# OpenChair.net
KiCad netlist of a schematic drawn in EAGLE
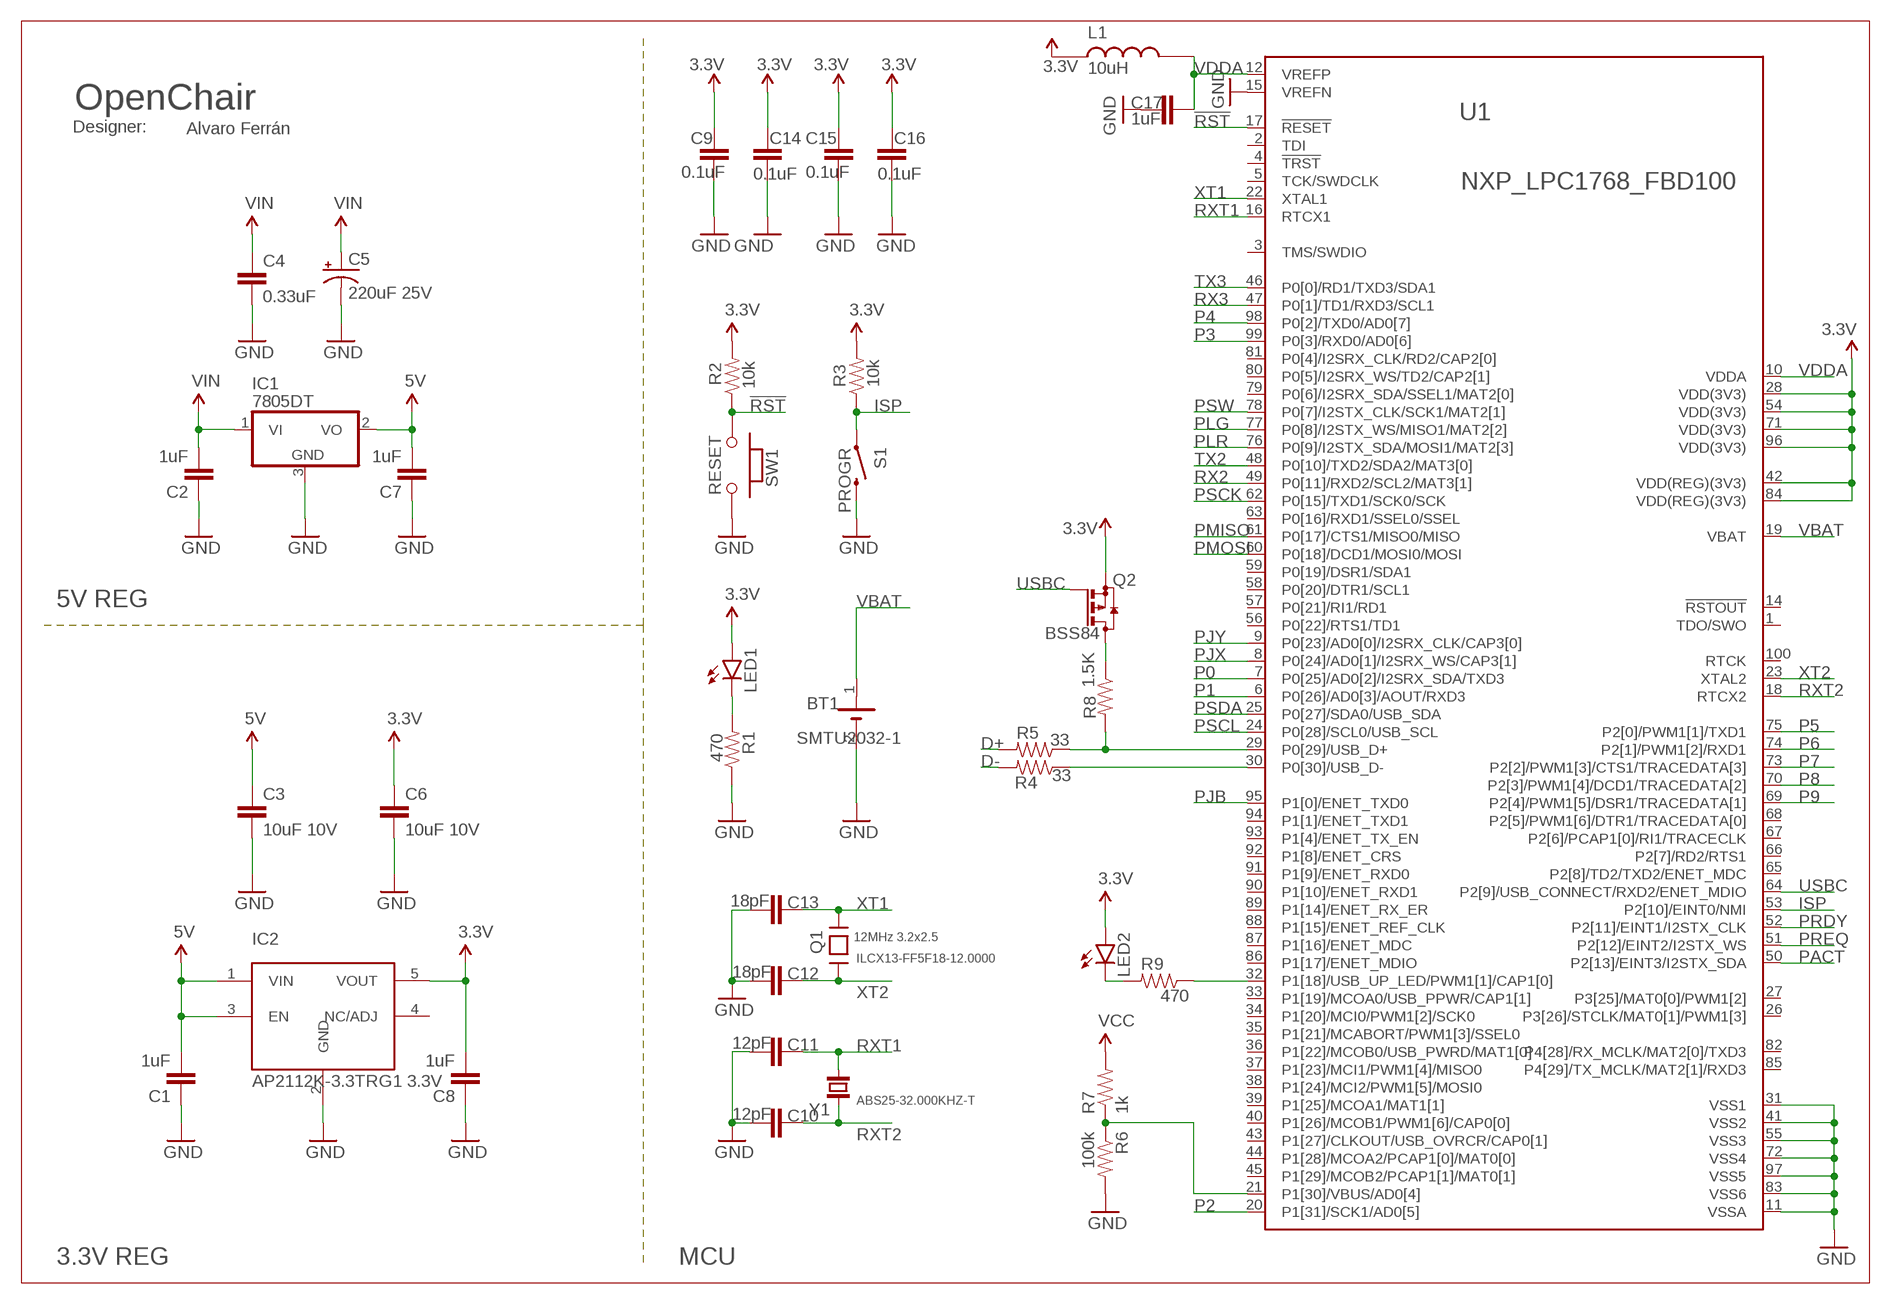
[diagram p0: schematic, sheet 1]
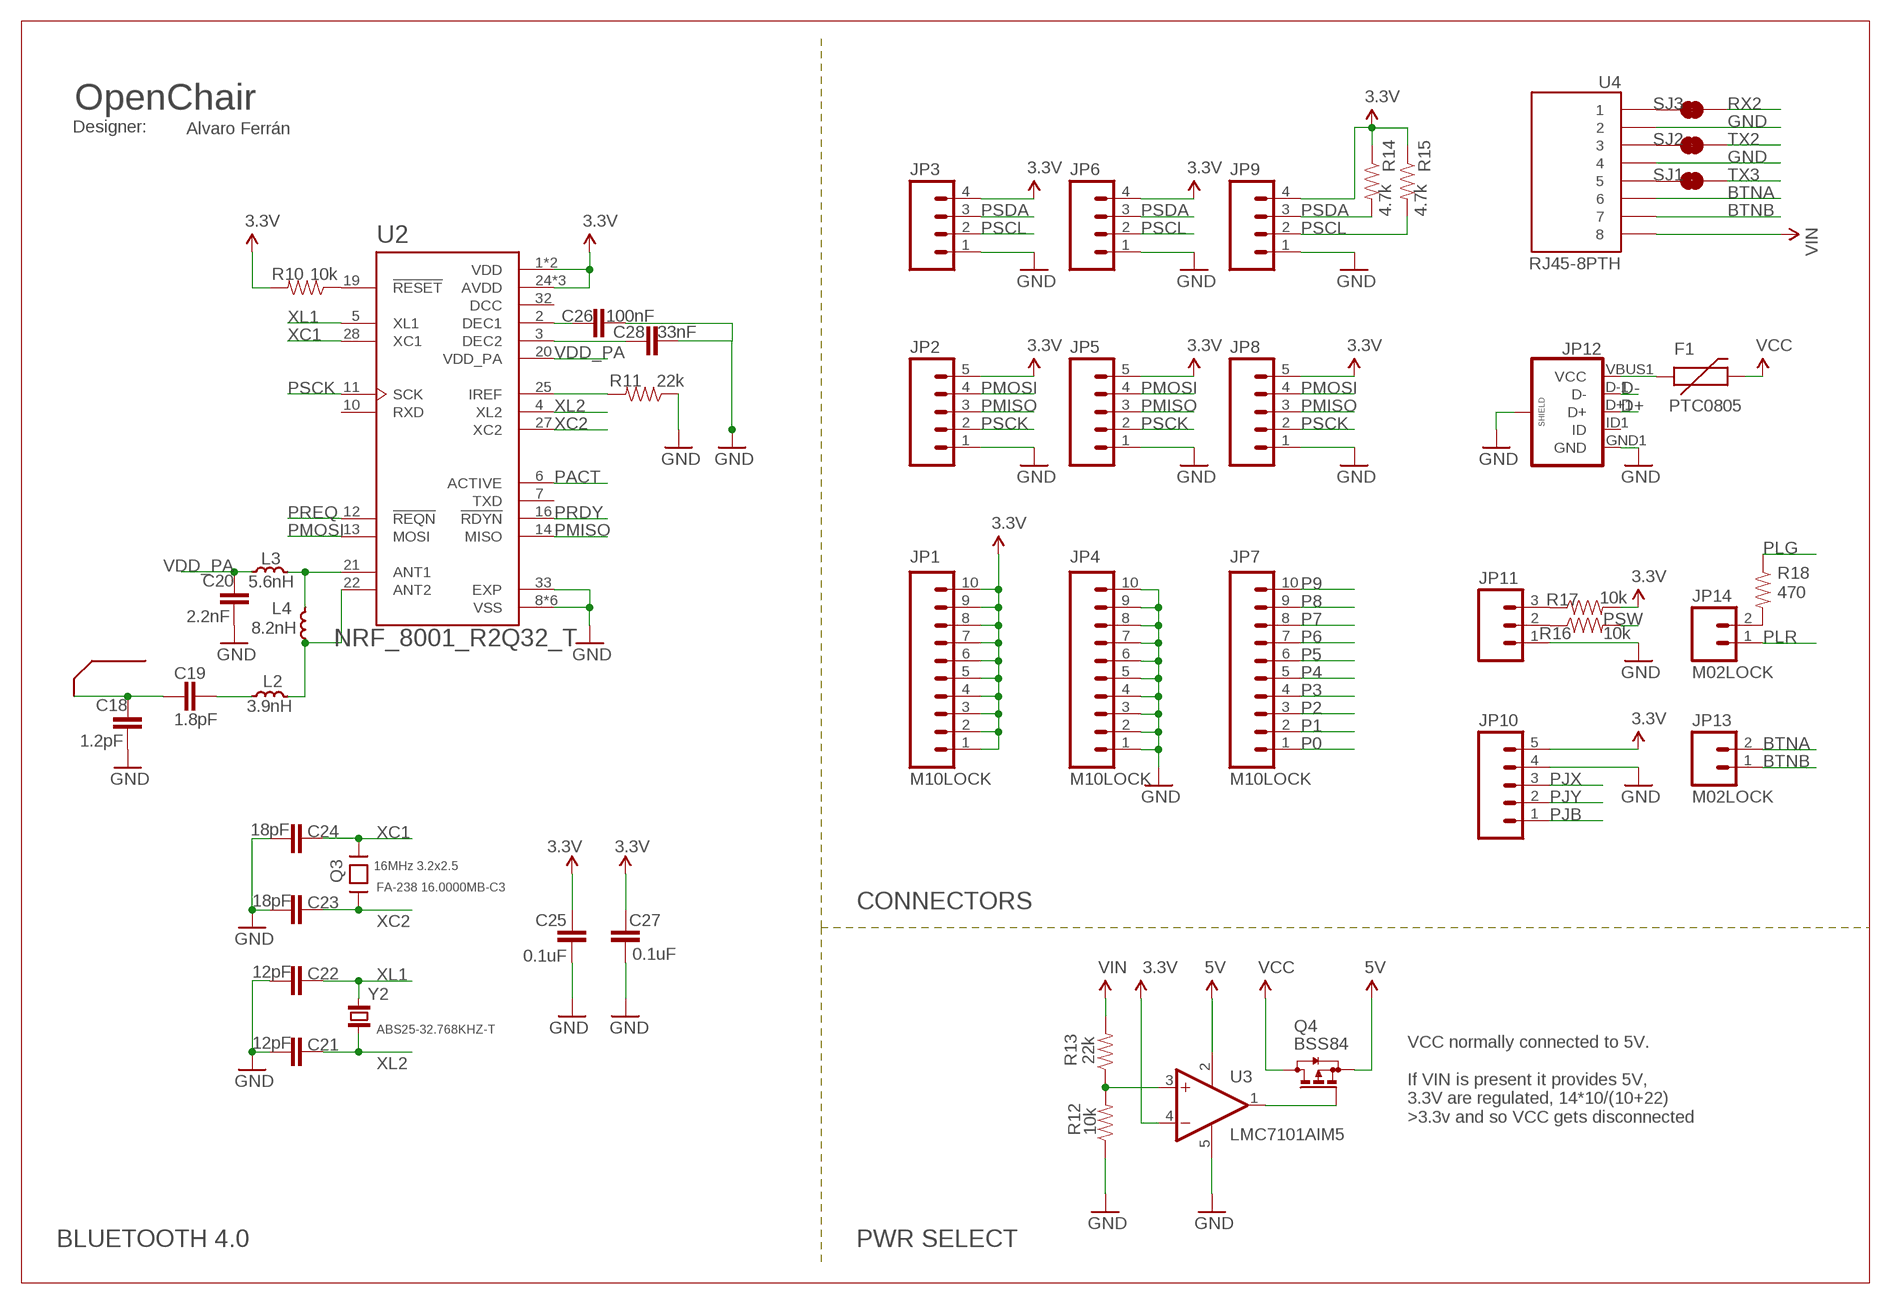
[diagram p1: schematic, sheet 2]

(export (version "E")
  (design (tool "Eeschema 10.0.6"))
  (components
    (comp (ref "ANT1")
      (value "NRF_ANTENNA")
      (footprint "eagle-import:NRF_ANTENNA")
      (libsource (lib "eagle-import") (part "NRF_ANTENNA"))
    )
    (comp (ref "C18")
      (value "1.2pF")
      (footprint "eagle-import:0402-CAP")
      (libsource (lib "eagle-import") (part "CAP0402-CAP"))
    )
    (comp (ref "C19")
      (value "1.8pF")
      (footprint "eagle-import:0402-CAP")
      (libsource (lib "eagle-import") (part "CAP0402-CAP"))
    )
    (comp (ref "C20")
      (value "2.2nF")
      (footprint "eagle-import:0402-CAP")
      (libsource (lib "eagle-import") (part "CAP0402-CAP"))
    )
    (comp (ref "C21")
      (value "12pF")
      (footprint "eagle-import:0402-CAP")
      (libsource (lib "eagle-import") (part "CAP0402-CAP"))
    )
    (comp (ref "C22")
      (value "12pF")
      (footprint "eagle-import:0402-CAP")
      (libsource (lib "eagle-import") (part "CAP0402-CAP"))
    )
    (comp (ref "C23")
      (value "18pF")
      (footprint "eagle-import:0402-CAP")
      (libsource (lib "eagle-import") (part "CAP0402-CAP"))
    )
    (comp (ref "C24")
      (value "18pF")
      (footprint "eagle-import:0402-CAP")
      (libsource (lib "eagle-import") (part "CAP0402-CAP"))
    )
    (comp (ref "C25")
      (value "0.1uF")
      (footprint "eagle-import:0402-CAP")
      (libsource (lib "eagle-import") (part "CAP0402-CAP"))
    )
    (comp (ref "C26")
      (value "100nF")
      (footprint "eagle-import:0402-CAP")
      (libsource (lib "eagle-import") (part "CAP0402-CAP"))
    )
    (comp (ref "C27")
      (value "0.1uF")
      (footprint "eagle-import:0402-CAP")
      (libsource (lib "eagle-import") (part "CAP0402-CAP"))
    )
    (comp (ref "C28")
      (value "33nF")
      (footprint "eagle-import:0402-CAP")
      (libsource (lib "eagle-import") (part "CAP0402-CAP"))
    )
    (comp (ref "F1")
      (value "PTC0805")
      (footprint "eagle-import:0805")
      (libsource (lib "eagle-import") (part "PTC0805"))
    )
    (comp (ref "JP1")
      (value "M10LOCK")
      (footprint "eagle-import:1X10_LOCK")
      (libsource (lib "eagle-import") (part "M10LOCK"))
    )
    (comp (ref "JP2")
      (value "M05LOCK")
      (footprint "eagle-import:1X05_LOCK")
      (libsource (lib "eagle-import") (part "M05LOCK"))
    )
    (comp (ref "JP3")
      (value "M04LOCK")
      (footprint "eagle-import:1X04_LOCK")
      (libsource (lib "eagle-import") (part "M04LOCK"))
    )
    (comp (ref "JP4")
      (value "M10LOCK")
      (footprint "eagle-import:1X10_LOCK")
      (libsource (lib "eagle-import") (part "M10LOCK"))
    )
    (comp (ref "JP5")
      (value "M05LOCK")
      (footprint "eagle-import:1X05_LOCK")
      (libsource (lib "eagle-import") (part "M05LOCK"))
    )
    (comp (ref "JP6")
      (value "M04LOCK")
      (footprint "eagle-import:1X04_LOCK")
      (libsource (lib "eagle-import") (part "M04LOCK"))
    )
    (comp (ref "JP7")
      (value "M10LOCK")
      (footprint "eagle-import:1X10_LOCK")
      (libsource (lib "eagle-import") (part "M10LOCK"))
    )
    (comp (ref "JP8")
      (value "M05LOCK")
      (footprint "eagle-import:1X05_LOCK")
      (libsource (lib "eagle-import") (part "M05LOCK"))
    )
    (comp (ref "JP9")
      (value "M04LOCK")
      (footprint "eagle-import:1X04_LOCK")
      (libsource (lib "eagle-import") (part "M04LOCK"))
    )
    (comp (ref "JP10")
      (value "M05LOCK")
      (footprint "eagle-import:1X05_LOCK")
      (libsource (lib "eagle-import") (part "M05LOCK"))
    )
    (comp (ref "JP11")
      (value "M03LOCK")
      (footprint "eagle-import:1X03_LOCK")
      (libsource (lib "eagle-import") (part "M03LOCK"))
    )
    (comp (ref "JP12")
      (value "USB_MICROB_PLUGCONN-11752")
      (footprint "eagle-import:USB-B-MICRO-SMD_V03")
      (libsource (lib "eagle-import") (part "USB_MICROB_PLUGCONN-11752"))
    )
    (comp (ref "JP13")
      (value "M02LOCK")
      (footprint "eagle-import:1X02_LOCK")
      (libsource (lib "eagle-import") (part "M02LOCK"))
    )
    (comp (ref "JP14")
      (value "M02LOCK")
      (footprint "eagle-import:1X02_LOCK")
      (libsource (lib "eagle-import") (part "M02LOCK"))
    )
    (comp (ref "L2")
      (value "3.9nH")
      (footprint "eagle-import:0402")
      (libsource (lib "eagle-import") (part "L0402"))
    )
    (comp (ref "L3")
      (value "5.6nH")
      (footprint "eagle-import:0402")
      (libsource (lib "eagle-import") (part "L0402"))
    )
    (comp (ref "L4")
      (value "8.2nH")
      (footprint "eagle-import:0402")
      (libsource (lib "eagle-import") (part "L0402"))
    )
    (comp (ref "Q3")
      (value "16MHz 3.2x2.5")
      (footprint "eagle-import:CRYSTAL_3.2X2.5")
      (libsource (lib "eagle-import") (part "CRYSTAL3.2X2.5"))
    )
    (comp (ref "Q4")
      (value "BSS84")
      (footprint "eagle-import:SOT23")
      (libsource (lib "eagle-import") (part "BSS84"))
    )
    (comp (ref "R10")
      (value "10k")
      (footprint "eagle-import:0402-RES")
      (libsource (lib "eagle-import") (part "RESISTOR0402-RES"))
    )
    (comp (ref "R11")
      (value "22k")
      (footprint "eagle-import:0402-RES")
      (libsource (lib "eagle-import") (part "RESISTOR0402-RES"))
    )
    (comp (ref "R12")
      (value "10k")
      (footprint "eagle-import:0402-RES")
      (libsource (lib "eagle-import") (part "RESISTOR0402-RES"))
    )
    (comp (ref "R13")
      (value "22k")
      (footprint "eagle-import:0402-RES")
      (libsource (lib "eagle-import") (part "RESISTOR0402-RES"))
    )
    (comp (ref "R14")
      (value "4.7k")
      (footprint "eagle-import:0402-RES")
      (libsource (lib "eagle-import") (part "RESISTOR0402-RES"))
    )
    (comp (ref "R15")
      (value "4.7k")
      (footprint "eagle-import:0402-RES")
      (libsource (lib "eagle-import") (part "RESISTOR0402-RES"))
    )
    (comp (ref "R16")
      (value "10k")
      (footprint "eagle-import:0402-RES")
      (libsource (lib "eagle-import") (part "RESISTOR0402-RES"))
    )
    (comp (ref "R17")
      (value "10k")
      (footprint "eagle-import:0402-RES")
      (libsource (lib "eagle-import") (part "RESISTOR0402-RES"))
    )
    (comp (ref "R18")
      (value "470")
      (footprint "eagle-import:0402-RES")
      (libsource (lib "eagle-import") (part "RESISTOR0402-RES"))
    )
    (comp (ref "SJ1")
      (value "JUMPER-PAD-2-NC_BY_TRACE")
      (footprint "eagle-import:PAD-JUMPER-2-NC_BY_TRACE_YES_SILK")
      (libsource (lib "eagle-import") (part "JUMPER-PAD-2-NC_BY_TRACE"))
    )
    (comp (ref "SJ2")
      (value "JUMPER-PAD-2-NC_BY_TRACE")
      (footprint "eagle-import:PAD-JUMPER-2-NC_BY_TRACE_YES_SILK")
      (libsource (lib "eagle-import") (part "JUMPER-PAD-2-NC_BY_TRACE"))
    )
    (comp (ref "SJ3")
      (value "JUMPER-PAD-2-NC_BY_TRACE")
      (footprint "eagle-import:PAD-JUMPER-2-NC_BY_TRACE_YES_SILK")
      (libsource (lib "eagle-import") (part "JUMPER-PAD-2-NC_BY_TRACE"))
    )
    (comp (ref "U2")
      (value "NRF_8001_R2Q32_T")
      (footprint "eagle-import:QFN50P500X500X90-33N")
      (fields (field (name "MF") "Nordic Semiconductor") (field (name "MP") "NRF8001-R2Q32-T"))
      (libsource (lib "eagle-import") (part "NRF_8001_R2Q32_T"))
    )
    (comp (ref "U3")
      (value "LMC7101AIM5")
      (footprint "eagle-import:SOT23-5")
      (libsource (lib "eagle-import") (part "LMC7101AIM5"))
    )
    (comp (ref "U4")
      (value "RJ45-8PTH")
      (footprint "eagle-import:RJ45-8")
      (libsource (lib "eagle-import") (part "RJ45-8PTH"))
    )
    (comp (ref "Y2")
      (value "ABS25-32.768kHz")
      (footprint "eagle-import:ABS25")
      (fields (field (name "MF") "Abracon") (field (name "MP") "ABS25-32.000KHZ-T"))
      (libsource (lib "eagle-import") (part "ABS25"))
    )
    (comp (ref "BT1")
      (value "SMTU2032-1")
      (footprint "eagle-import:RENATA_SMTU2032-1")
      (fields (field (name "MF") "Renata") (field (name "MP") "SMTU2032-LF.TR"))
      (libsource (lib "eagle-import") (part "SMTU2032-1"))
    )
    (comp (ref "C1")
      (value "1uF")
      (footprint "eagle-import:0603-CAP")
      (libsource (lib "eagle-import") (part "CAP0603-CAP"))
    )
    (comp (ref "C2")
      (value "1uF")
      (footprint "eagle-import:0603-CAP")
      (libsource (lib "eagle-import") (part "CAP0603-CAP"))
    )
    (comp (ref "C3")
      (value "10uF 10V")
      (footprint "eagle-import:0603-CAP")
      (libsource (lib "eagle-import") (part "CAP0603-CAP"))
    )
    (comp (ref "C4")
      (value "0.33uF")
      (footprint "eagle-import:0805")
      (libsource (lib "eagle-import") (part "CAP0805"))
    )
    (comp (ref "C5")
      (value "220uF 25V")
      (footprint "eagle-import:CPOL-RADIAL-100UF-25V")
      (libsource (lib "eagle-import") (part "CAP_POLPTH1"))
    )
    (comp (ref "C6")
      (value "10uF 10V")
      (footprint "eagle-import:0603-CAP")
      (libsource (lib "eagle-import") (part "CAP0603-CAP"))
    )
    (comp (ref "C7")
      (value "1uF")
      (footprint "eagle-import:0603-CAP")
      (libsource (lib "eagle-import") (part "CAP0603-CAP"))
    )
    (comp (ref "C8")
      (value "1uF")
      (footprint "eagle-import:0603-CAP")
      (libsource (lib "eagle-import") (part "CAP0603-CAP"))
    )
    (comp (ref "C9")
      (value "0.1uF")
      (footprint "eagle-import:0402-CAP")
      (libsource (lib "eagle-import") (part "CAP0402-CAP"))
    )
    (comp (ref "C10")
      (value "12pF")
      (footprint "eagle-import:0402-CAP")
      (libsource (lib "eagle-import") (part "CAP0402-CAP"))
    )
    (comp (ref "C11")
      (value "12pF")
      (footprint "eagle-import:0402-CAP")
      (libsource (lib "eagle-import") (part "CAP0402-CAP"))
    )
    (comp (ref "C12")
      (value "18pF")
      (footprint "eagle-import:0402-CAP")
      (libsource (lib "eagle-import") (part "CAP0402-CAP"))
    )
    (comp (ref "C13")
      (value "18pF")
      (footprint "eagle-import:0402-CAP")
      (libsource (lib "eagle-import") (part "CAP0402-CAP"))
    )
    (comp (ref "C14")
      (value "0.1uF")
      (footprint "eagle-import:0402-CAP")
      (libsource (lib "eagle-import") (part "CAP0402-CAP"))
    )
    (comp (ref "C15")
      (value "0.1uF")
      (footprint "eagle-import:0402-CAP")
      (libsource (lib "eagle-import") (part "CAP0402-CAP"))
    )
    (comp (ref "C16")
      (value "0.1uF")
      (footprint "eagle-import:0402-CAP")
      (libsource (lib "eagle-import") (part "CAP0402-CAP"))
    )
    (comp (ref "C17")
      (value "1uF")
      (footprint "eagle-import:0603-CAP")
      (libsource (lib "eagle-import") (part "CAP0603-CAP"))
    )
    (comp (ref "IC1")
      (value "7805DT")
      (footprint "eagle-import:TO252")
      (libsource (lib "eagle-import") (part "78DT05"))
    )
    (comp (ref "IC2")
      (value "AP2112K-3.3TRG1 3.3V")
      (footprint "eagle-import:SOT23-5")
      (libsource (lib "eagle-import") (part "5PIN_REG"))
    )
    (comp (ref "L1")
      (value "10uH")
      (footprint "eagle-import:L0603")
      (libsource (lib "eagle-import") (part "L_L"))
    )
    (comp (ref "LED1")
      (value "LED0603")
      (footprint "eagle-import:LED-0603")
      (libsource (lib "eagle-import") (part "LED0603"))
    )
    (comp (ref "LED2")
      (value "LED0603")
      (footprint "eagle-import:LED-0603")
      (libsource (lib "eagle-import") (part "LED0603"))
    )
    (comp (ref "Q1")
      (value "12MHz 3.2x2.5")
      (footprint "eagle-import:CRYSTAL_3.2X2.5")
      (libsource (lib "eagle-import") (part "CRYSTAL3.2X2.5"))
    )
    (comp (ref "Q2")
      (value "BSS84")
      (footprint "eagle-import:SOT23")
      (libsource (lib "eagle-import") (part "BSS84"))
    )
    (comp (ref "R1")
      (value "470")
      (footprint "eagle-import:0402-RES")
      (libsource (lib "eagle-import") (part "RESISTOR0402-RES"))
    )
    (comp (ref "R2")
      (value "10k")
      (footprint "eagle-import:0402-RES")
      (libsource (lib "eagle-import") (part "RESISTOR0402-RES"))
    )
    (comp (ref "R3")
      (value "10k")
      (footprint "eagle-import:0402-RES")
      (libsource (lib "eagle-import") (part "RESISTOR0402-RES"))
    )
    (comp (ref "R4")
      (value "33")
      (footprint "eagle-import:0402-RES")
      (libsource (lib "eagle-import") (part "RESISTOR0402-RES"))
    )
    (comp (ref "R5")
      (value "33")
      (footprint "eagle-import:0402-RES")
      (libsource (lib "eagle-import") (part "RESISTOR0402-RES"))
    )
    (comp (ref "R6")
      (value "100k")
      (footprint "eagle-import:0402-RES")
      (libsource (lib "eagle-import") (part "RESISTOR0402-RES"))
    )
    (comp (ref "R7")
      (value "1k")
      (footprint "eagle-import:0402-RES")
      (libsource (lib "eagle-import") (part "RESISTOR0402-RES"))
    )
    (comp (ref "R8")
      (value "1.5K")
      (footprint "eagle-import:0402-RES")
      (libsource (lib "eagle-import") (part "RESISTOR0402-RES"))
    )
    (comp (ref "R9")
      (value "470")
      (footprint "eagle-import:0402-RES")
      (libsource (lib "eagle-import") (part "RESISTOR0402-RES"))
    )
    (comp (ref "S1")
      (value "PROGR")
      (footprint "eagle-import:TACTILE-PTH-SIDEEZ")
      (libsource (lib "eagle-import") (part "SWITCH-MOMENTARY-2SIDE_EZ"))
    )
    (comp (ref "SW1")
      (value "RESET")
      (footprint "eagle-import:157SW")
      (libsource (lib "eagle-import") (part "PB157"))
    )
    (comp (ref "U1")
      (value "NXP_LPC1768_FBD100")
      (footprint "eagle-import:QFP50P1600X1600X160-100N")
      (fields (field (name "MF") "NXP Semiconductors") (field (name "MP") "LPC1768FBD100,551"))
      (libsource (lib "eagle-import") (part "NXP_LPC1768_FBD100"))
    )
    (comp (ref "Y1")
      (value "ABS25")
      (footprint "eagle-import:ABS25")
      (fields (field (name "MF") "Abracon") (field (name "MP") "ABS25-32.000KHZ-T"))
      (libsource (lib "eagle-import") (part "ABS25"))
    )
  )
  (nets
    (net (code "1") (name "3.3V") (class "Default")
      (node (ref "C14") (pin "1") (pinfunction "1_1") (pintype "passive"))
      (node (ref "C15") (pin "1") (pinfunction "1_1") (pintype "passive"))
      (node (ref "C16") (pin "1") (pinfunction "1_1") (pintype "passive"))
      (node (ref "C25") (pin "1") (pinfunction "1_1") (pintype "passive"))
      (node (ref "C27") (pin "1") (pinfunction "1_1") (pintype "passive"))
      (node (ref "C6") (pin "1") (pinfunction "1_1") (pintype "passive"))
      (node (ref "C8") (pin "2") (pinfunction "2_2") (pintype "passive"))
      (node (ref "C9") (pin "1") (pinfunction "1_1") (pintype "passive"))
      (node (ref "IC2") (pin "5") (pinfunction "VOUT_5") (pintype "bidirectional"))
      (node (ref "JP1") (pin "1") (pinfunction "1_1") (pintype "passive"))
      (node (ref "JP1") (pin "10") (pinfunction "10_10") (pintype "passive"))
      (node (ref "JP1") (pin "2") (pinfunction "2_2") (pintype "passive"))
      (node (ref "JP1") (pin "3") (pinfunction "3_3") (pintype "passive"))
      (node (ref "JP1") (pin "4") (pinfunction "4_4") (pintype "passive"))
      (node (ref "JP1") (pin "5") (pinfunction "5_5") (pintype "passive"))
      (node (ref "JP1") (pin "6") (pinfunction "6_6") (pintype "passive"))
      (node (ref "JP1") (pin "7") (pinfunction "7_7") (pintype "passive"))
      (node (ref "JP1") (pin "8") (pinfunction "8_8") (pintype "passive"))
      (node (ref "JP1") (pin "9") (pinfunction "9_9") (pintype "passive"))
      (node (ref "JP10") (pin "5") (pinfunction "5_5") (pintype "passive"))
      (node (ref "JP2") (pin "5") (pinfunction "5_5") (pintype "passive"))
      (node (ref "JP3") (pin "4") (pinfunction "4_4") (pintype "passive"))
      (node (ref "JP5") (pin "5") (pinfunction "5_5") (pintype "passive"))
      (node (ref "JP6") (pin "4") (pinfunction "4_4") (pintype "passive"))
      (node (ref "JP8") (pin "5") (pinfunction "5_5") (pintype "passive"))
      (node (ref "JP9") (pin "4") (pinfunction "4_4") (pintype "passive"))
      (node (ref "L1") (pin "P$1") (pinfunction "P$1_P$1") (pintype "bidirectional"))
      (node (ref "LED1") (pin "A") (pinfunction "A_A") (pintype "passive"))
      (node (ref "LED2") (pin "A") (pinfunction "A_A") (pintype "passive"))
      (node (ref "Q2") (pin "2") (pinfunction "S_2") (pintype "passive"))
      (node (ref "R10") (pin "2") (pinfunction "2_2") (pintype "passive"))
      (node (ref "R14") (pin "1") (pinfunction "1_1") (pintype "passive"))
      (node (ref "R15") (pin "1") (pinfunction "1_1") (pintype "passive"))
      (node (ref "R17") (pin "2") (pinfunction "2_2") (pintype "passive"))
      (node (ref "R2") (pin "2") (pinfunction "2_2") (pintype "passive"))
      (node (ref "R3") (pin "2") (pinfunction "2_2") (pintype "passive"))
      (node (ref "U1") (pin "28") (pinfunction "VDD(3V3)_28") (pintype "power_in"))
      (node (ref "U1") (pin "42") (pinfunction "VDD(REG)(3V3)_42") (pintype "power_in"))
      (node (ref "U1") (pin "54") (pinfunction "VDD(3V3)_54") (pintype "power_in"))
      (node (ref "U1") (pin "71") (pinfunction "VDD(3V3)_71") (pintype "power_in"))
      (node (ref "U1") (pin "84") (pinfunction "VDD(REG)(3V3)_84") (pintype "power_in"))
      (node (ref "U1") (pin "96") (pinfunction "VDD(3V3)_96") (pintype "power_in"))
      (node (ref "U2") (pin "1") (pinfunction "VDD_1") (pintype "power_in"))
      (node (ref "U2") (pin "24") (pinfunction "AVDD_24") (pintype "power_in"))
      (node (ref "U2") (pin "26") (pinfunction "AVDD_26") (pintype "power_in"))
      (node (ref "U2") (pin "29") (pinfunction "AVDD_29") (pintype "power_in"))
      (node (ref "U2") (pin "9") (pinfunction "VDD_9") (pintype "power_in"))
      (node (ref "U3") (pin "4") (pinfunction "-IN_4") (pintype "input"))
    )
    (net (code "2") (name "5V") (class "Default")
      (node (ref "C1") (pin "2") (pinfunction "2_2") (pintype "passive"))
      (node (ref "C3") (pin "1") (pinfunction "1_1") (pintype "passive"))
      (node (ref "C7") (pin "2") (pinfunction "2_2") (pintype "passive"))
      (node (ref "IC1") (pin "2") (pinfunction "VO_2") (pintype "passive"))
      (node (ref "IC2") (pin "1") (pinfunction "VIN_1") (pintype "bidirectional"))
      (node (ref "IC2") (pin "3") (pinfunction "EN_3") (pintype "bidirectional"))
      (node (ref "Q4") (pin "2") (pinfunction "S_2") (pintype "passive"))
      (node (ref "U3") (pin "2") (pinfunction "V+_2") (pintype "power_in"))
    )
    (net (code "3") (name "BTNA") (class "Default")
      (node (ref "JP13") (pin "2") (pinfunction "2_2") (pintype "passive"))
      (node (ref "U4") (pin "6") (pinfunction "6_6") (pintype "bidirectional"))
    )
    (net (code "4") (name "BTNB") (class "Default")
      (node (ref "JP13") (pin "1") (pinfunction "1_1") (pintype "passive"))
      (node (ref "U4") (pin "7") (pinfunction "7_7") (pintype "bidirectional"))
    )
    (net (code "5") (name "D+") (class "Default")
      (node (ref "JP12") (pin "D+1") (pinfunction "D+_D+1") (pintype "bidirectional"))
      (node (ref "R5") (pin "2") (pinfunction "2_2") (pintype "passive"))
    )
    (net (code "6") (name "D-") (class "Default")
      (node (ref "JP12") (pin "D-1") (pinfunction "D-_D-1") (pintype "bidirectional"))
      (node (ref "R4") (pin "2") (pinfunction "2_2") (pintype "passive"))
    )
    (net (code "7") (name "DCC") (class "Default")
      (node (ref "U2") (pin "32") (pinfunction "DCC_32") (pintype "power_in"))
    )
    (net (code "8") (name "GND") (class "Default")
      (node (ref "BT1") (pin "2") (pinfunction "-_2") (pintype "passive"))
      (node (ref "C1") (pin "1") (pinfunction "1_1") (pintype "passive"))
      (node (ref "C10") (pin "2") (pinfunction "2_2") (pintype "passive"))
      (node (ref "C11") (pin "2") (pinfunction "2_2") (pintype "passive"))
      (node (ref "C12") (pin "2") (pinfunction "2_2") (pintype "passive"))
      (node (ref "C13") (pin "2") (pinfunction "2_2") (pintype "passive"))
      (node (ref "C14") (pin "2") (pinfunction "2_2") (pintype "passive"))
      (node (ref "C15") (pin "2") (pinfunction "2_2") (pintype "passive"))
      (node (ref "C16") (pin "2") (pinfunction "2_2") (pintype "passive"))
      (node (ref "C17") (pin "1") (pinfunction "1_1") (pintype "passive"))
      (node (ref "C18") (pin "2") (pinfunction "2_2") (pintype "passive"))
      (node (ref "C2") (pin "1") (pinfunction "1_1") (pintype "passive"))
      (node (ref "C20") (pin "2") (pinfunction "2_2") (pintype "passive"))
      (node (ref "C21") (pin "2") (pinfunction "2_2") (pintype "passive"))
      (node (ref "C22") (pin "2") (pinfunction "2_2") (pintype "passive"))
      (node (ref "C23") (pin "2") (pinfunction "2_2") (pintype "passive"))
      (node (ref "C24") (pin "2") (pinfunction "2_2") (pintype "passive"))
      (node (ref "C25") (pin "2") (pinfunction "2_2") (pintype "passive"))
      (node (ref "C26") (pin "1") (pinfunction "1_1") (pintype "passive"))
      (node (ref "C27") (pin "2") (pinfunction "2_2") (pintype "passive"))
      (node (ref "C28") (pin "1") (pinfunction "1_1") (pintype "passive"))
      (node (ref "C3") (pin "2") (pinfunction "2_2") (pintype "passive"))
      (node (ref "C4") (pin "2") (pinfunction "2_2") (pintype "passive"))
      (node (ref "C5") (pin "2") (pinfunction "-_2") (pintype "passive"))
      (node (ref "C6") (pin "2") (pinfunction "2_2") (pintype "passive"))
      (node (ref "C7") (pin "1") (pinfunction "1_1") (pintype "passive"))
      (node (ref "C8") (pin "1") (pinfunction "1_1") (pintype "passive"))
      (node (ref "C9") (pin "2") (pinfunction "2_2") (pintype "passive"))
      (node (ref "IC1") (pin "3") (pinfunction "GND_3") (pintype "passive"))
      (node (ref "IC2") (pin "2") (pinfunction "GND_2") (pintype "bidirectional"))
      (node (ref "JP10") (pin "4") (pinfunction "4_4") (pintype "passive"))
      (node (ref "JP11") (pin "1") (pinfunction "1_1") (pintype "passive"))
      (node (ref "JP12") (pin "GND1") (pinfunction "GND_GND1") (pintype "bidirectional"))
      (node (ref "JP12") (pin "SHIELD1") (pinfunction "SHIELD_SHIELD1") (pintype "bidirectional"))
      (node (ref "JP12") (pin "SHIELD2") (pinfunction "SHIELD_SHIELD2") (pintype "bidirectional"))
      (node (ref "JP12") (pin "SHIELD3") (pinfunction "SHIELD_SHIELD3") (pintype "bidirectional"))
      (node (ref "JP2") (pin "1") (pinfunction "1_1") (pintype "passive"))
      (node (ref "JP3") (pin "1") (pinfunction "1_1") (pintype "passive"))
      (node (ref "JP4") (pin "1") (pinfunction "1_1") (pintype "passive"))
      (node (ref "JP4") (pin "10") (pinfunction "10_10") (pintype "passive"))
      (node (ref "JP4") (pin "2") (pinfunction "2_2") (pintype "passive"))
      (node (ref "JP4") (pin "3") (pinfunction "3_3") (pintype "passive"))
      (node (ref "JP4") (pin "4") (pinfunction "4_4") (pintype "passive"))
      (node (ref "JP4") (pin "5") (pinfunction "5_5") (pintype "passive"))
      (node (ref "JP4") (pin "6") (pinfunction "6_6") (pintype "passive"))
      (node (ref "JP4") (pin "7") (pinfunction "7_7") (pintype "passive"))
      (node (ref "JP4") (pin "8") (pinfunction "8_8") (pintype "passive"))
      (node (ref "JP4") (pin "9") (pinfunction "9_9") (pintype "passive"))
      (node (ref "JP5") (pin "1") (pinfunction "1_1") (pintype "passive"))
      (node (ref "JP6") (pin "1") (pinfunction "1_1") (pintype "passive"))
      (node (ref "JP8") (pin "1") (pinfunction "1_1") (pintype "passive"))
      (node (ref "JP9") (pin "1") (pinfunction "1_1") (pintype "passive"))
      (node (ref "R1") (pin "1") (pinfunction "1_1") (pintype "passive"))
      (node (ref "R11") (pin "1") (pinfunction "1_1") (pintype "passive"))
      (node (ref "R12") (pin "1") (pinfunction "1_1") (pintype "passive"))
      (node (ref "R6") (pin "2") (pinfunction "2_2") (pintype "passive"))
      (node (ref "S1") (pin "2") (pinfunction "2_2") (pintype "passive"))
      (node (ref "SW1") (pin "2") (pinfunction "2_2") (pintype "passive"))
      (node (ref "U1") (pin "11") (pinfunction "VSSA_11") (pintype "power_in"))
      (node (ref "U1") (pin "15") (pinfunction "VREFN_15") (pintype "input"))
      (node (ref "U1") (pin "31") (pinfunction "VSS1_31") (pintype "power_in"))
      (node (ref "U1") (pin "41") (pinfunction "VSS2_41") (pintype "power_in"))
      (node (ref "U1") (pin "55") (pinfunction "VSS3_55") (pintype "power_in"))
      (node (ref "U1") (pin "72") (pinfunction "VSS4_72") (pintype "power_in"))
      (node (ref "U1") (pin "83") (pinfunction "VSS6_83") (pintype "power_in"))
      (node (ref "U1") (pin "97") (pinfunction "VSS5_97") (pintype "power_in"))
      (node (ref "U2") (pin "17") (pinfunction "VSS_17") (pintype "power_in"))
      (node (ref "U2") (pin "18") (pinfunction "VSS_18") (pintype "power_in"))
      (node (ref "U2") (pin "23") (pinfunction "VSS_23") (pintype "power_in"))
      (node (ref "U2") (pin "30") (pinfunction "VSS_30") (pintype "power_in"))
      (node (ref "U2") (pin "31") (pinfunction "VSS_31") (pintype "power_in"))
      (node (ref "U2") (pin "33") (pinfunction "EXP_33") (pintype "power_in"))
      (node (ref "U2") (pin "8") (pinfunction "VSS_8") (pintype "power_in"))
      (node (ref "U3") (pin "5") (pinfunction "V-_5") (pintype "power_in"))
      (node (ref "U4") (pin "2") (pinfunction "2_2") (pintype "bidirectional"))
      (node (ref "U4") (pin "4") (pinfunction "4_4") (pintype "bidirectional"))
    )
    (net (code "9") (name "ISP") (class "Default")
      (node (ref "R3") (pin "1") (pinfunction "1_1") (pintype "passive"))
      (node (ref "S1") (pin "1") (pinfunction "1_1") (pintype "passive"))
      (node (ref "U1") (pin "53") (pinfunction "P2[10]/EINT0/NMI_53") (pintype "bidirectional"))
    )
    (net (code "10") (name "Net-(ANT1-PadP$1)") (class "Default")
      (node (ref "ANT1") (pin "P$1") (pinfunction "P$1_P$1") (pintype "bidirectional"))
      (node (ref "C18") (pin "1") (pinfunction "1_1") (pintype "passive"))
      (node (ref "C19") (pin "2") (pinfunction "2_2") (pintype "passive"))
    )
    (net (code "11") (name "Net-(JP11-Pad2)") (class "Default")
      (node (ref "JP11") (pin "2") (pinfunction "2_2") (pintype "passive"))
      (node (ref "R16") (pin "1") (pinfunction "1_1") (pintype "passive"))
    )
    (net (code "12") (name "Net-(JP11-Pad3)") (class "Default")
      (node (ref "JP11") (pin "3") (pinfunction "3_3") (pintype "passive"))
      (node (ref "R17") (pin "1") (pinfunction "1_1") (pintype "passive"))
    )
    (net (code "13") (name "Net-(JP12-VCC)") (class "Default")
      (node (ref "F1") (pin "1") (pinfunction "1_1") (pintype "bidirectional"))
      (node (ref "JP12") (pin "VBUS1") (pinfunction "VCC_VBUS1") (pintype "bidirectional"))
    )
    (net (code "14") (name "Net-(JP14-Pad2)") (class "Default")
      (node (ref "JP14") (pin "2") (pinfunction "2_2") (pintype "passive"))
      (node (ref "R18") (pin "2") (pinfunction "2_2") (pintype "passive"))
    )
    (net (code "15") (name "Net-(L2-P$1)") (class "Default")
      (node (ref "C19") (pin "1") (pinfunction "1_1") (pintype "passive"))
      (node (ref "L2") (pin "1") (pinfunction "P$1_1") (pintype "bidirectional"))
    )
    (net (code "16") (name "Net-(L2-P$2)") (class "Default")
      (node (ref "L2") (pin "2") (pinfunction "P$2_2") (pintype "bidirectional"))
      (node (ref "L4") (pin "1") (pinfunction "P$1_1") (pintype "bidirectional"))
      (node (ref "U2") (pin "22") (pinfunction "ANT2_22") (pintype "passive"))
    )
    (net (code "17") (name "Net-(L3-P$2)") (class "Default")
      (node (ref "L3") (pin "2") (pinfunction "P$2_2") (pintype "bidirectional"))
      (node (ref "L4") (pin "2") (pinfunction "P$2_2") (pintype "bidirectional"))
      (node (ref "U2") (pin "21") (pinfunction "ANT1_21") (pintype "passive"))
    )
    (net (code "18") (name "Net-(LED1-PadC)") (class "Default")
      (node (ref "LED1") (pin "C") (pinfunction "C_C") (pintype "passive"))
      (node (ref "R1") (pin "2") (pinfunction "2_2") (pintype "passive"))
    )
    (net (code "19") (name "Net-(LED2-PadC)") (class "Default")
      (node (ref "LED2") (pin "C") (pinfunction "C_C") (pintype "passive"))
      (node (ref "R9") (pin "2") (pinfunction "2_2") (pintype "passive"))
    )
    (net (code "20") (name "Net-(Q2-D)") (class "Default")
      (node (ref "Q2") (pin "3") (pinfunction "D_3") (pintype "passive"))
      (node (ref "R8") (pin "1") (pinfunction "1_1") (pintype "passive"))
    )
    (net (code "21") (name "Net-(Q4-G)") (class "Default")
      (node (ref "Q4") (pin "1") (pinfunction "G_1") (pintype "passive"))
      (node (ref "U3") (pin "1") (pinfunction "OUT_1") (pintype "output"))
    )
    (net (code "22") (name "Net-(SJ1-Pad1)") (class "Default")
      (node (ref "SJ1") (pin "1") (pinfunction "1_1") (pintype "passive"))
      (node (ref "U4") (pin "5") (pinfunction "5_5") (pintype "bidirectional"))
    )
    (net (code "23") (name "Net-(SJ2-Pad1)") (class "Default")
      (node (ref "SJ2") (pin "1") (pinfunction "1_1") (pintype "passive"))
      (node (ref "U4") (pin "3") (pinfunction "3_3") (pintype "bidirectional"))
    )
    (net (code "24") (name "Net-(SJ3-Pad1)") (class "Default")
      (node (ref "SJ3") (pin "1") (pinfunction "1_1") (pintype "passive"))
      (node (ref "U4") (pin "1") (pinfunction "1_1") (pintype "bidirectional"))
    )
    (net (code "25") (name "Net-(U1-P0[29]{slash}USB_D+)") (class "Default")
      (node (ref "R5") (pin "1") (pinfunction "1_1") (pintype "passive"))
      (node (ref "R8") (pin "2") (pinfunction "2_2") (pintype "passive"))
      (node (ref "U1") (pin "29") (pinfunction "P0[29]/USB_D+_29") (pintype "bidirectional"))
    )
    (net (code "26") (name "Net-(U1-P0[30]{slash}USB_D-)") (class "Default")
      (node (ref "R4") (pin "1") (pinfunction "1_1") (pintype "passive"))
      (node (ref "U1") (pin "30") (pinfunction "P0[30]/USB_D-_30") (pintype "bidirectional"))
    )
    (net (code "27") (name "Net-(U1-P1[18]{slash}USB_UP_LED{slash}PWM1[1]{slash}CAP1[0])") (class "Default")
      (node (ref "R9") (pin "1") (pinfunction "1_1") (pintype "passive"))
      (node (ref "U1") (pin "32") (pinfunction "P1[18]/USB_UP_LED/PWM1[1]/CAP1[0]_32") (pintype "bidirectional"))
    )
    (net (code "28") (name "Net-(U1-P1[30]{slash}VBUS{slash}AD0[4])") (class "Default")
      (node (ref "R6") (pin "1") (pinfunction "1_1") (pintype "passive"))
      (node (ref "R7") (pin "1") (pinfunction "1_1") (pintype "passive"))
      (node (ref "U1") (pin "21") (pinfunction "P1[30]/VBUS/AD0[4]_21") (pintype "bidirectional"))
    )
    (net (code "29") (name "Net-(U2-DEC1)") (class "Default")
      (node (ref "C26") (pin "2") (pinfunction "2_2") (pintype "passive"))
      (node (ref "U2") (pin "2") (pinfunction "DEC1_2") (pintype "power_in"))
    )
    (net (code "30") (name "Net-(U2-DEC2)") (class "Default")
      (node (ref "C28") (pin "2") (pinfunction "2_2") (pintype "passive"))
      (node (ref "U2") (pin "3") (pinfunction "DEC2_3") (pintype "power_in"))
    )
    (net (code "31") (name "Net-(U2-IREF)") (class "Default")
      (node (ref "R11") (pin "2") (pinfunction "2_2") (pintype "passive"))
      (node (ref "U2") (pin "25") (pinfunction "IREF_25") (pintype "output"))
    )
    (net (code "32") (name "Net-(U2-~{RESET})") (class "Default")
      (node (ref "R10") (pin "1") (pinfunction "1_1") (pintype "passive"))
      (node (ref "U2") (pin "19") (pinfunction "~{RESET}_19") (pintype "input"))
    )
    (net (code "33") (name "Net-(U3-+IN)") (class "Default")
      (node (ref "R12") (pin "2") (pinfunction "2_2") (pintype "passive"))
      (node (ref "R13") (pin "1") (pinfunction "1_1") (pintype "passive"))
      (node (ref "U3") (pin "3") (pinfunction "+IN_3") (pintype "input"))
    )
    (net (code "34") (name "P0") (class "Default")
      (node (ref "JP7") (pin "1") (pinfunction "1_1") (pintype "passive"))
      (node (ref "U1") (pin "7") (pinfunction "P0[25]/AD0[2]/I2SRX_SDA/TXD3_7") (pintype "bidirectional"))
    )
    (net (code "35") (name "P1") (class "Default")
      (node (ref "JP7") (pin "2") (pinfunction "2_2") (pintype "passive"))
      (node (ref "U1") (pin "6") (pinfunction "P0[26]/AD0[3]/AOUT/RXD3_6") (pintype "bidirectional"))
    )
    (net (code "36") (name "P2") (class "Default")
      (node (ref "JP7") (pin "3") (pinfunction "3_3") (pintype "passive"))
      (node (ref "U1") (pin "20") (pinfunction "P1[31]/SCK1/AD0[5]_20") (pintype "bidirectional"))
    )
    (net (code "37") (name "P3") (class "Default")
      (node (ref "JP7") (pin "4") (pinfunction "4_4") (pintype "passive"))
      (node (ref "U1") (pin "99") (pinfunction "P0[3]/RXD0/AD0[6]_99") (pintype "bidirectional"))
    )
    (net (code "38") (name "P4") (class "Default")
      (node (ref "JP7") (pin "5") (pinfunction "5_5") (pintype "passive"))
      (node (ref "U1") (pin "98") (pinfunction "P0[2]/TXD0/AD0[7]_98") (pintype "bidirectional"))
    )
    (net (code "39") (name "P5") (class "Default")
      (node (ref "JP7") (pin "6") (pinfunction "6_6") (pintype "passive"))
      (node (ref "U1") (pin "75") (pinfunction "P2[0]/PWM1[1]/TXD1_75") (pintype "bidirectional"))
    )
    (net (code "40") (name "P6") (class "Default")
      (node (ref "JP7") (pin "7") (pinfunction "7_7") (pintype "passive"))
      (node (ref "U1") (pin "74") (pinfunction "P2[1]/PWM1[2]/RXD1_74") (pintype "bidirectional"))
    )
    (net (code "41") (name "P7") (class "Default")
      (node (ref "JP7") (pin "8") (pinfunction "8_8") (pintype "passive"))
      (node (ref "U1") (pin "73") (pinfunction "P2[2]/PWM1[3]/CTS1/TRACEDATA[3]_73") (pintype "bidirectional"))
    )
    (net (code "42") (name "P8") (class "Default")
      (node (ref "JP7") (pin "9") (pinfunction "9_9") (pintype "passive"))
      (node (ref "U1") (pin "70") (pinfunction "P2[3]/PWM1[4]/DCD1/TRACEDATA[2]_70") (pintype "bidirectional"))
    )
    (net (code "43") (name "P9") (class "Default")
      (node (ref "JP7") (pin "10") (pinfunction "10_10") (pintype "passive"))
      (node (ref "U1") (pin "69") (pinfunction "P2[4]/PWM1[5]/DSR1/TRACEDATA[1]_69") (pintype "bidirectional"))
    )
    (net (code "44") (name "PACT") (class "Default")
      (node (ref "U1") (pin "50") (pinfunction "P2[13]/EINT3/I2STX_SDA_50") (pintype "bidirectional"))
      (node (ref "U2") (pin "6") (pinfunction "ACTIVE_6") (pintype "output"))
    )
    (net (code "45") (name "PJB") (class "Default")
      (node (ref "JP10") (pin "1") (pinfunction "1_1") (pintype "passive"))
      (node (ref "U1") (pin "95") (pinfunction "P1[0]/ENET_TXD0_95") (pintype "bidirectional"))
    )
    (net (code "46") (name "PJX") (class "Default")
      (node (ref "JP10") (pin "3") (pinfunction "3_3") (pintype "passive"))
      (node (ref "U1") (pin "8") (pinfunction "P0[24]/AD0[1]/I2SRX_WS/CAP3[1]_8") (pintype "bidirectional"))
    )
    (net (code "47") (name "PJY") (class "Default")
      (node (ref "JP10") (pin "2") (pinfunction "2_2") (pintype "passive"))
      (node (ref "U1") (pin "9") (pinfunction "P0[23]/AD0[0]/I2SRX_CLK/CAP3[0]_9") (pintype "bidirectional"))
    )
    (net (code "48") (name "PLG") (class "Default")
      (node (ref "R18") (pin "1") (pinfunction "1_1") (pintype "passive"))
      (node (ref "U1") (pin "77") (pinfunction "P0[8]/I2STX_WS/MISO1/MAT2[2]_77") (pintype "bidirectional"))
    )
    (net (code "49") (name "PLR") (class "Default")
      (node (ref "JP14") (pin "1") (pinfunction "1_1") (pintype "passive"))
      (node (ref "U1") (pin "76") (pinfunction "P0[9]/I2STX_SDA/MOSI1/MAT2[3]_76") (pintype "bidirectional"))
    )
    (net (code "50") (name "PMISO") (class "Default")
      (node (ref "JP2") (pin "3") (pinfunction "3_3") (pintype "passive"))
      (node (ref "JP5") (pin "3") (pinfunction "3_3") (pintype "passive"))
      (node (ref "JP8") (pin "3") (pinfunction "3_3") (pintype "passive"))
      (node (ref "U1") (pin "61") (pinfunction "P0[17]/CTS1/MISO0/MISO_61") (pintype "bidirectional"))
      (node (ref "U2") (pin "14") (pinfunction "MISO_14") (pintype "output"))
    )
    (net (code "51") (name "PMOSI") (class "Default")
      (node (ref "JP2") (pin "4") (pinfunction "4_4") (pintype "passive"))
      (node (ref "JP5") (pin "4") (pinfunction "4_4") (pintype "passive"))
      (node (ref "JP8") (pin "4") (pinfunction "4_4") (pintype "passive"))
      (node (ref "U1") (pin "60") (pinfunction "P0[18]/DCD1/MOSI0/MOSI_60") (pintype "bidirectional"))
      (node (ref "U2") (pin "13") (pinfunction "MOSI_13") (pintype "input"))
    )
    (net (code "52") (name "PRDY") (class "Default")
      (node (ref "U1") (pin "52") (pinfunction "P2[11]/EINT1/I2STX_CLK_52") (pintype "bidirectional"))
      (node (ref "U2") (pin "16") (pinfunction "~{RDYN}_16") (pintype "output"))
    )
    (net (code "53") (name "PREQ") (class "Default")
      (node (ref "U1") (pin "51") (pinfunction "P2[12]/EINT2/I2STX_WS_51") (pintype "bidirectional"))
      (node (ref "U2") (pin "12") (pinfunction "~{REQN}_12") (pintype "input"))
    )
    (net (code "54") (name "PSCK") (class "Default")
      (node (ref "JP2") (pin "2") (pinfunction "2_2") (pintype "passive"))
      (node (ref "JP5") (pin "2") (pinfunction "2_2") (pintype "passive"))
      (node (ref "JP8") (pin "2") (pinfunction "2_2") (pintype "passive"))
      (node (ref "U1") (pin "62") (pinfunction "P0[15]/TXD1/SCK0/SCK_62") (pintype "bidirectional"))
      (node (ref "U2") (pin "11") (pinfunction "SCK_11") (pintype "input"))
    )
    (net (code "55") (name "PSCL") (class "Default")
      (node (ref "JP3") (pin "2") (pinfunction "2_2") (pintype "passive"))
      (node (ref "JP6") (pin "2") (pinfunction "2_2") (pintype "passive"))
      (node (ref "JP9") (pin "2") (pinfunction "2_2") (pintype "passive"))
      (node (ref "R15") (pin "2") (pinfunction "2_2") (pintype "passive"))
      (node (ref "U1") (pin "24") (pinfunction "P0[28]/SCL0/USB_SCL_24") (pintype "bidirectional"))
    )
    (net (code "56") (name "PSDA") (class "Default")
      (node (ref "JP3") (pin "3") (pinfunction "3_3") (pintype "passive"))
      (node (ref "JP6") (pin "3") (pinfunction "3_3") (pintype "passive"))
      (node (ref "JP9") (pin "3") (pinfunction "3_3") (pintype "passive"))
      (node (ref "R14") (pin "2") (pinfunction "2_2") (pintype "passive"))
      (node (ref "U1") (pin "25") (pinfunction "P0[27]/SDA0/USB_SDA_25") (pintype "bidirectional"))
    )
    (net (code "57") (name "PSW") (class "Default")
      (node (ref "R16") (pin "2") (pinfunction "2_2") (pintype "passive"))
      (node (ref "U1") (pin "78") (pinfunction "P0[7]/I2STX_CLK/SCK1/MAT2[1]_78") (pintype "bidirectional"))
    )
    (net (code "58") (name "RX2") (class "Default")
      (node (ref "SJ3") (pin "2") (pinfunction "2_2") (pintype "passive"))
      (node (ref "U1") (pin "49") (pinfunction "P0[11]/RXD2/SCL2/MAT3[1]_49") (pintype "bidirectional"))
    )
    (net (code "59") (name "RX3") (class "Default")
      (node (ref "U1") (pin "47") (pinfunction "P0[1]/TD1/RXD3/SCL1_47") (pintype "bidirectional"))
    )
    (net (code "60") (name "RXT1") (class "Default")
      (node (ref "C11") (pin "1") (pinfunction "1_1") (pintype "passive"))
      (node (ref "U1") (pin "16") (pinfunction "RTCX1_16") (pintype "input"))
      (node (ref "Y1") (pin "1") (pinfunction "1_1") (pintype "passive"))
    )
    (net (code "61") (name "RXT2") (class "Default")
      (node (ref "C10") (pin "1") (pinfunction "1_1") (pintype "passive"))
      (node (ref "U1") (pin "18") (pinfunction "RTCX2_18") (pintype "output"))
      (node (ref "Y1") (pin "4") (pinfunction "2_4") (pintype "passive"))
    )
    (net (code "62") (name "TX2") (class "Default")
      (node (ref "SJ2") (pin "2") (pinfunction "2_2") (pintype "passive"))
      (node (ref "U1") (pin "48") (pinfunction "P0[10]/TXD2/SDA2/MAT3[0]_48") (pintype "bidirectional"))
    )
    (net (code "63") (name "TX3") (class "Default")
      (node (ref "SJ1") (pin "2") (pinfunction "2_2") (pintype "passive"))
      (node (ref "U1") (pin "46") (pinfunction "P0[0]/RD1/TXD3/SDA1_46") (pintype "bidirectional"))
    )
    (net (code "64") (name "USBC") (class "Default")
      (node (ref "Q2") (pin "1") (pinfunction "G_1") (pintype "passive"))
      (node (ref "U1") (pin "64") (pinfunction "P2[9]/USB_CONNECT/RXD2/ENET_MDIO_64") (pintype "bidirectional"))
    )
    (net (code "65") (name "VBAT") (class "Default")
      (node (ref "BT1") (pin "1") (pinfunction "+_1") (pintype "passive"))
      (node (ref "U1") (pin "19") (pinfunction "VBAT_19") (pintype "power_in"))
    )
    (net (code "66") (name "VCC") (class "Default")
      (node (ref "F1") (pin "2") (pinfunction "2_2") (pintype "bidirectional"))
      (node (ref "Q4") (pin "3") (pinfunction "D_3") (pintype "passive"))
      (node (ref "R7") (pin "2") (pinfunction "2_2") (pintype "passive"))
    )
    (net (code "67") (name "VDDA") (class "Default")
      (node (ref "C17") (pin "2") (pinfunction "2_2") (pintype "passive"))
      (node (ref "L1") (pin "P$2") (pinfunction "P$2_P$2") (pintype "bidirectional"))
      (node (ref "U1") (pin "10") (pinfunction "VDDA_10") (pintype "power_in"))
      (node (ref "U1") (pin "12") (pinfunction "VREFP_12") (pintype "input"))
    )
    (net (code "68") (name "VDD_PA") (class "Default")
      (node (ref "C20") (pin "1") (pinfunction "1_1") (pintype "passive"))
      (node (ref "L3") (pin "1") (pinfunction "P$1_1") (pintype "bidirectional"))
      (node (ref "U2") (pin "20") (pinfunction "VDD_PA_20") (pintype "output"))
    )
    (net (code "69") (name "VIN") (class "Default")
      (node (ref "C2") (pin "2") (pinfunction "2_2") (pintype "passive"))
      (node (ref "C4") (pin "1") (pinfunction "1_1") (pintype "passive"))
      (node (ref "C5") (pin "1") (pinfunction "+_1") (pintype "passive"))
      (node (ref "IC1") (pin "1") (pinfunction "VI_1") (pintype "input"))
      (node (ref "R13") (pin "2") (pinfunction "2_2") (pintype "passive"))
      (node (ref "U4") (pin "8") (pinfunction "8_8") (pintype "bidirectional"))
    )
    (net (code "70") (name "XC1") (class "Default")
      (node (ref "C24") (pin "1") (pinfunction "1_1") (pintype "passive"))
      (node (ref "Q3") (pin "3") (pinfunction "P$2_3") (pintype "passive"))
      (node (ref "U2") (pin "28") (pinfunction "XC1_28") (pintype "input"))
    )
    (net (code "71") (name "XC2") (class "Default")
      (node (ref "C23") (pin "1") (pinfunction "1_1") (pintype "passive"))
      (node (ref "Q3") (pin "1") (pinfunction "P$1_1") (pintype "passive"))
      (node (ref "U2") (pin "27") (pinfunction "XC2_27") (pintype "output"))
    )
    (net (code "72") (name "XL1") (class "Default")
      (node (ref "C22") (pin "1") (pinfunction "1_1") (pintype "passive"))
      (node (ref "U2") (pin "5") (pinfunction "XL1_5") (pintype "input"))
      (node (ref "Y2") (pin "4") (pinfunction "2_4") (pintype "passive"))
    )
    (net (code "73") (name "XL2") (class "Default")
      (node (ref "C21") (pin "1") (pinfunction "1_1") (pintype "passive"))
      (node (ref "U2") (pin "4") (pinfunction "XL2_4") (pintype "output"))
      (node (ref "Y2") (pin "1") (pinfunction "1_1") (pintype "passive"))
    )
    (net (code "74") (name "XT1") (class "Default")
      (node (ref "C13") (pin "1") (pinfunction "1_1") (pintype "passive"))
      (node (ref "Q1") (pin "3") (pinfunction "P$2_3") (pintype "passive"))
      (node (ref "U1") (pin "22") (pinfunction "XTAL1_22") (pintype "input"))
    )
    (net (code "75") (name "XT2") (class "Default")
      (node (ref "C12") (pin "1") (pinfunction "1_1") (pintype "passive"))
      (node (ref "Q1") (pin "1") (pinfunction "P$1_1") (pintype "passive"))
      (node (ref "U1") (pin "23") (pinfunction "XTAL2_23") (pintype "output"))
    )
    (net (code "76") (name "unconnected-(IC2-NC{slash}ADJ-Pad4)") (class "Default")
      (node (ref "IC2") (pin "4") (pinfunction "NC/ADJ_4") (pintype "bidirectional"))
    )
    (net (code "77") (name "unconnected-(JP12-ID-PadID1)") (class "Default")
      (node (ref "JP12") (pin "ID1") (pinfunction "ID_ID1") (pintype "bidirectional"))
    )
    (net (code "78") (name "unconnected-(U1-P0[4]{slash}I2SRX_CLK{slash}RD2{slash}CAP2[0]-Pad81)") (class "Default")
      (node (ref "U1") (pin "81") (pinfunction "P0[4]/I2SRX_CLK/RD2/CAP2[0]_81") (pintype "bidirectional"))
    )
    (net (code "79") (name "unconnected-(U1-P0[5]{slash}I2SRX_WS{slash}TD2{slash}CAP2[1]-Pad80)") (class "Default")
      (node (ref "U1") (pin "80") (pinfunction "P0[5]/I2SRX_WS/TD2/CAP2[1]_80") (pintype "bidirectional"))
    )
    (net (code "80") (name "unconnected-(U1-P0[6]{slash}I2SRX_SDA{slash}SSEL1{slash}MAT2[0]-Pad79)") (class "Default")
      (node (ref "U1") (pin "79") (pinfunction "P0[6]/I2SRX_SDA/SSEL1/MAT2[0]_79") (pintype "bidirectional"))
    )
    (net (code "81") (name "unconnected-(U1-P0[16]{slash}RXD1{slash}SSEL0{slash}SSEL-Pad63)") (class "Default")
      (node (ref "U1") (pin "63") (pinfunction "P0[16]/RXD1/SSEL0/SSEL_63") (pintype "bidirectional"))
    )
    (net (code "82") (name "unconnected-(U1-P0[19]{slash}DSR1{slash}SDA1-Pad59)") (class "Default")
      (node (ref "U1") (pin "59") (pinfunction "P0[19]/DSR1/SDA1_59") (pintype "bidirectional"))
    )
    (net (code "83") (name "unconnected-(U1-P0[20]{slash}DTR1{slash}SCL1-Pad58)") (class "Default")
      (node (ref "U1") (pin "58") (pinfunction "P0[20]/DTR1/SCL1_58") (pintype "bidirectional"))
    )
    (net (code "84") (name "unconnected-(U1-P0[21]{slash}RI1{slash}RD1-Pad57)") (class "Default")
      (node (ref "U1") (pin "57") (pinfunction "P0[21]/RI1/RD1_57") (pintype "bidirectional"))
    )
    (net (code "85") (name "unconnected-(U1-P0[22]{slash}RTS1{slash}TD1-Pad56)") (class "Default")
      (node (ref "U1") (pin "56") (pinfunction "P0[22]/RTS1/TD1_56") (pintype "bidirectional"))
    )
    (net (code "86") (name "unconnected-(U1-P1[1]{slash}ENET_TXD1-Pad94)") (class "Default")
      (node (ref "U1") (pin "94") (pinfunction "P1[1]/ENET_TXD1_94") (pintype "bidirectional"))
    )
    (net (code "87") (name "unconnected-(U1-P1[4]{slash}ENET_TX_EN-Pad93)") (class "Default")
      (node (ref "U1") (pin "93") (pinfunction "P1[4]/ENET_TX_EN_93") (pintype "bidirectional"))
    )
    (net (code "88") (name "unconnected-(U1-P1[8]{slash}ENET_CRS-Pad92)") (class "Default")
      (node (ref "U1") (pin "92") (pinfunction "P1[8]/ENET_CRS_92") (pintype "bidirectional"))
    )
    (net (code "89") (name "unconnected-(U1-P1[9]{slash}ENET_RXD0-Pad91)") (class "Default")
      (node (ref "U1") (pin "91") (pinfunction "P1[9]/ENET_RXD0_91") (pintype "bidirectional"))
    )
    (net (code "90") (name "unconnected-(U1-P1[10]{slash}ENET_RXD1-Pad90)") (class "Default")
      (node (ref "U1") (pin "90") (pinfunction "P1[10]/ENET_RXD1_90") (pintype "bidirectional"))
    )
    (net (code "91") (name "unconnected-(U1-P1[14]{slash}ENET_RX_ER-Pad89)") (class "Default")
      (node (ref "U1") (pin "89") (pinfunction "P1[14]/ENET_RX_ER_89") (pintype "bidirectional"))
    )
    (net (code "92") (name "unconnected-(U1-P1[15]{slash}ENET_REF_CLK-Pad88)") (class "Default")
      (node (ref "U1") (pin "88") (pinfunction "P1[15]/ENET_REF_CLK_88") (pintype "bidirectional"))
    )
    (net (code "93") (name "unconnected-(U1-P1[16]{slash}ENET_MDC-Pad87)") (class "Default")
      (node (ref "U1") (pin "87") (pinfunction "P1[16]/ENET_MDC_87") (pintype "bidirectional"))
    )
    (net (code "94") (name "unconnected-(U1-P1[17]{slash}ENET_MDIO-Pad86)") (class "Default")
      (node (ref "U1") (pin "86") (pinfunction "P1[17]/ENET_MDIO_86") (pintype "bidirectional"))
    )
    (net (code "95") (name "unconnected-(U1-P1[19]{slash}MCOA0{slash}USB_PPWR{slash}CAP1[1]-Pad33)") (class "Default")
      (node (ref "U1") (pin "33") (pinfunction "P1[19]/MCOA0/USB_PPWR/CAP1[1]_33") (pintype "bidirectional"))
    )
    (net (code "96") (name "unconnected-(U1-P1[20]{slash}MCI0{slash}PWM1[2]{slash}SCK0-Pad34)") (class "Default")
      (node (ref "U1") (pin "34") (pinfunction "P1[20]/MCI0/PWM1[2]/SCK0_34") (pintype "bidirectional"))
    )
    (net (code "97") (name "unconnected-(U1-P1[21]{slash}MCABORT{slash}PWM1[3]{slash}SSEL0-Pad35)") (class "Default")
      (node (ref "U1") (pin "35") (pinfunction "P1[21]/MCABORT/PWM1[3]/SSEL0_35") (pintype "bidirectional"))
    )
    (net (code "98") (name "unconnected-(U1-P1[22]{slash}MCOB0{slash}USB_PWRD{slash}MAT1[0]-Pad36)") (class "Default")
      (node (ref "U1") (pin "36") (pinfunction "P1[22]/MCOB0/USB_PWRD/MAT1[0]_36") (pintype "bidirectional"))
    )
    (net (code "99") (name "unconnected-(U1-P1[23]{slash}MCI1{slash}PWM1[4]{slash}MISO0-Pad37)") (class "Default")
      (node (ref "U1") (pin "37") (pinfunction "P1[23]/MCI1/PWM1[4]/MISO0_37") (pintype "bidirectional"))
    )
    (net (code "100") (name "unconnected-(U1-P1[24]{slash}MCI2{slash}PWM1[5]{slash}MOSI0-Pad38)") (class "Default")
      (node (ref "U1") (pin "38") (pinfunction "P1[24]/MCI2/PWM1[5]/MOSI0_38") (pintype "bidirectional"))
    )
    (net (code "101") (name "unconnected-(U1-P1[25]{slash}MCOA1{slash}MAT1[1]-Pad39)") (class "Default")
      (node (ref "U1") (pin "39") (pinfunction "P1[25]/MCOA1/MAT1[1]_39") (pintype "bidirectional"))
    )
    (net (code "102") (name "unconnected-(U1-P1[26]{slash}MCOB1{slash}PWM1[6]{slash}CAP0[0]-Pad40)") (class "Default")
      (node (ref "U1") (pin "40") (pinfunction "P1[26]/MCOB1/PWM1[6]/CAP0[0]_40") (pintype "bidirectional"))
    )
    (net (code "103") (name "unconnected-(U1-P1[27]{slash}CLKOUT{slash}USB_OVRCR{slash}CAP0[1]-Pad43)") (class "Default")
      (node (ref "U1") (pin "43") (pinfunction "P1[27]/CLKOUT/USB_OVRCR/CAP0[1]_43") (pintype "bidirectional"))
    )
    (net (code "104") (name "unconnected-(U1-P1[28]{slash}MCOA2{slash}PCAP1[0]{slash}MAT0[0]-Pad44)") (class "Default")
      (node (ref "U1") (pin "44") (pinfunction "P1[28]/MCOA2/PCAP1[0]/MAT0[0]_44") (pintype "bidirectional"))
    )
    (net (code "105") (name "unconnected-(U1-P1[29]{slash}MCOB2{slash}PCAP1[1]{slash}MAT0[1]-Pad45)") (class "Default")
      (node (ref "U1") (pin "45") (pinfunction "P1[29]/MCOB2/PCAP1[1]/MAT0[1]_45") (pintype "bidirectional"))
    )
    (net (code "106") (name "unconnected-(U1-P2[5]{slash}PWM1[6]{slash}DTR1{slash}TRACEDATA[0]-Pad68)") (class "Default")
      (node (ref "U1") (pin "68") (pinfunction "P2[5]/PWM1[6]/DTR1/TRACEDATA[0]_68") (pintype "bidirectional"))
    )
    (net (code "107") (name "unconnected-(U1-P2[6]{slash}PCAP1[0]{slash}RI1{slash}TRACECLK-Pad67)") (class "Default")
      (node (ref "U1") (pin "67") (pinfunction "P2[6]/PCAP1[0]/RI1/TRACECLK_67") (pintype "bidirectional"))
    )
    (net (code "108") (name "unconnected-(U1-P2[7]{slash}RD2{slash}RTS1-Pad66)") (class "Default")
      (node (ref "U1") (pin "66") (pinfunction "P2[7]/RD2/RTS1_66") (pintype "bidirectional"))
    )
    (net (code "109") (name "unconnected-(U1-P2[8]{slash}TD2{slash}TXD2{slash}ENET_MDC-Pad65)") (class "Default")
      (node (ref "U1") (pin "65") (pinfunction "P2[8]/TD2/TXD2/ENET_MDC_65") (pintype "bidirectional"))
    )
    (net (code "110") (name "unconnected-(U1-P3[25]{slash}MAT0[0]{slash}PWM1[2]-Pad27)") (class "Default")
      (node (ref "U1") (pin "27") (pinfunction "P3[25]/MAT0[0]/PWM1[2]_27") (pintype "bidirectional"))
    )
    (net (code "111") (name "unconnected-(U1-P3[26]{slash}STCLK{slash}MAT0[1]{slash}PWM1[3]-Pad26)") (class "Default")
      (node (ref "U1") (pin "26") (pinfunction "P3[26]/STCLK/MAT0[1]/PWM1[3]_26") (pintype "bidirectional"))
    )
    (net (code "112") (name "unconnected-(U1-P4[28]{slash}RX_MCLK{slash}MAT2[0]{slash}TXD3-Pad82)") (class "Default")
      (node (ref "U1") (pin "82") (pinfunction "P4[28]/RX_MCLK/MAT2[0]/TXD3_82") (pintype "bidirectional"))
    )
    (net (code "113") (name "unconnected-(U1-P4[29]{slash}TX_MCLK{slash}MAT2[1]{slash}RXD3-Pad85)") (class "Default")
      (node (ref "U1") (pin "85") (pinfunction "P4[29]/TX_MCLK/MAT2[1]/RXD3_85") (pintype "bidirectional"))
    )
    (net (code "114") (name "unconnected-(U1-RTCK-Pad100)") (class "Default")
      (node (ref "U1") (pin "100") (pinfunction "RTCK_100") (pintype "output"))
    )
    (net (code "115") (name "unconnected-(U1-TCK{slash}SWDCLK-Pad5)") (class "Default")
      (node (ref "U1") (pin "5") (pinfunction "TCK/SWDCLK_5") (pintype "input"))
    )
    (net (code "116") (name "unconnected-(U1-TDI-Pad2)") (class "Default")
      (node (ref "U1") (pin "2") (pinfunction "TDI_2") (pintype "input"))
    )
    (net (code "117") (name "unconnected-(U1-TDO{slash}SWO-Pad1)") (class "Default")
      (node (ref "U1") (pin "1") (pinfunction "TDO/SWO_1") (pintype "output"))
    )
    (net (code "118") (name "unconnected-(U1-TMS{slash}SWDIO-Pad3)") (class "Default")
      (node (ref "U1") (pin "3") (pinfunction "TMS/SWDIO_3") (pintype "bidirectional"))
    )
    (net (code "119") (name "unconnected-(U1-~{RSTOUT}-Pad14)") (class "Default")
      (node (ref "U1") (pin "14") (pinfunction "~{RSTOUT}_14") (pintype "output"))
    )
    (net (code "120") (name "unconnected-(U1-~{TRST}-Pad4)") (class "Default")
      (node (ref "U1") (pin "4") (pinfunction "~{TRST}_4") (pintype "input"))
    )
    (net (code "121") (name "unconnected-(U2-RXD-Pad10)") (class "Default")
      (node (ref "U2") (pin "10") (pinfunction "RXD_10") (pintype "input"))
    )
    (net (code "122") (name "unconnected-(U2-TXD-Pad7)") (class "Default")
      (node (ref "U2") (pin "7") (pinfunction "TXD_7") (pintype "output"))
    )
    (net (code "123") (name "~{RST}") (class "Default")
      (node (ref "R2") (pin "1") (pinfunction "1_1") (pintype "passive"))
      (node (ref "SW1") (pin "1") (pinfunction "1_1") (pintype "passive"))
      (node (ref "U1") (pin "17") (pinfunction "~{RESET}_17") (pintype "input"))
    )
  )
)
